# MSSRP-Bluetooth_IF.net
KiCad netlist of a schematic drawn in EAGLE
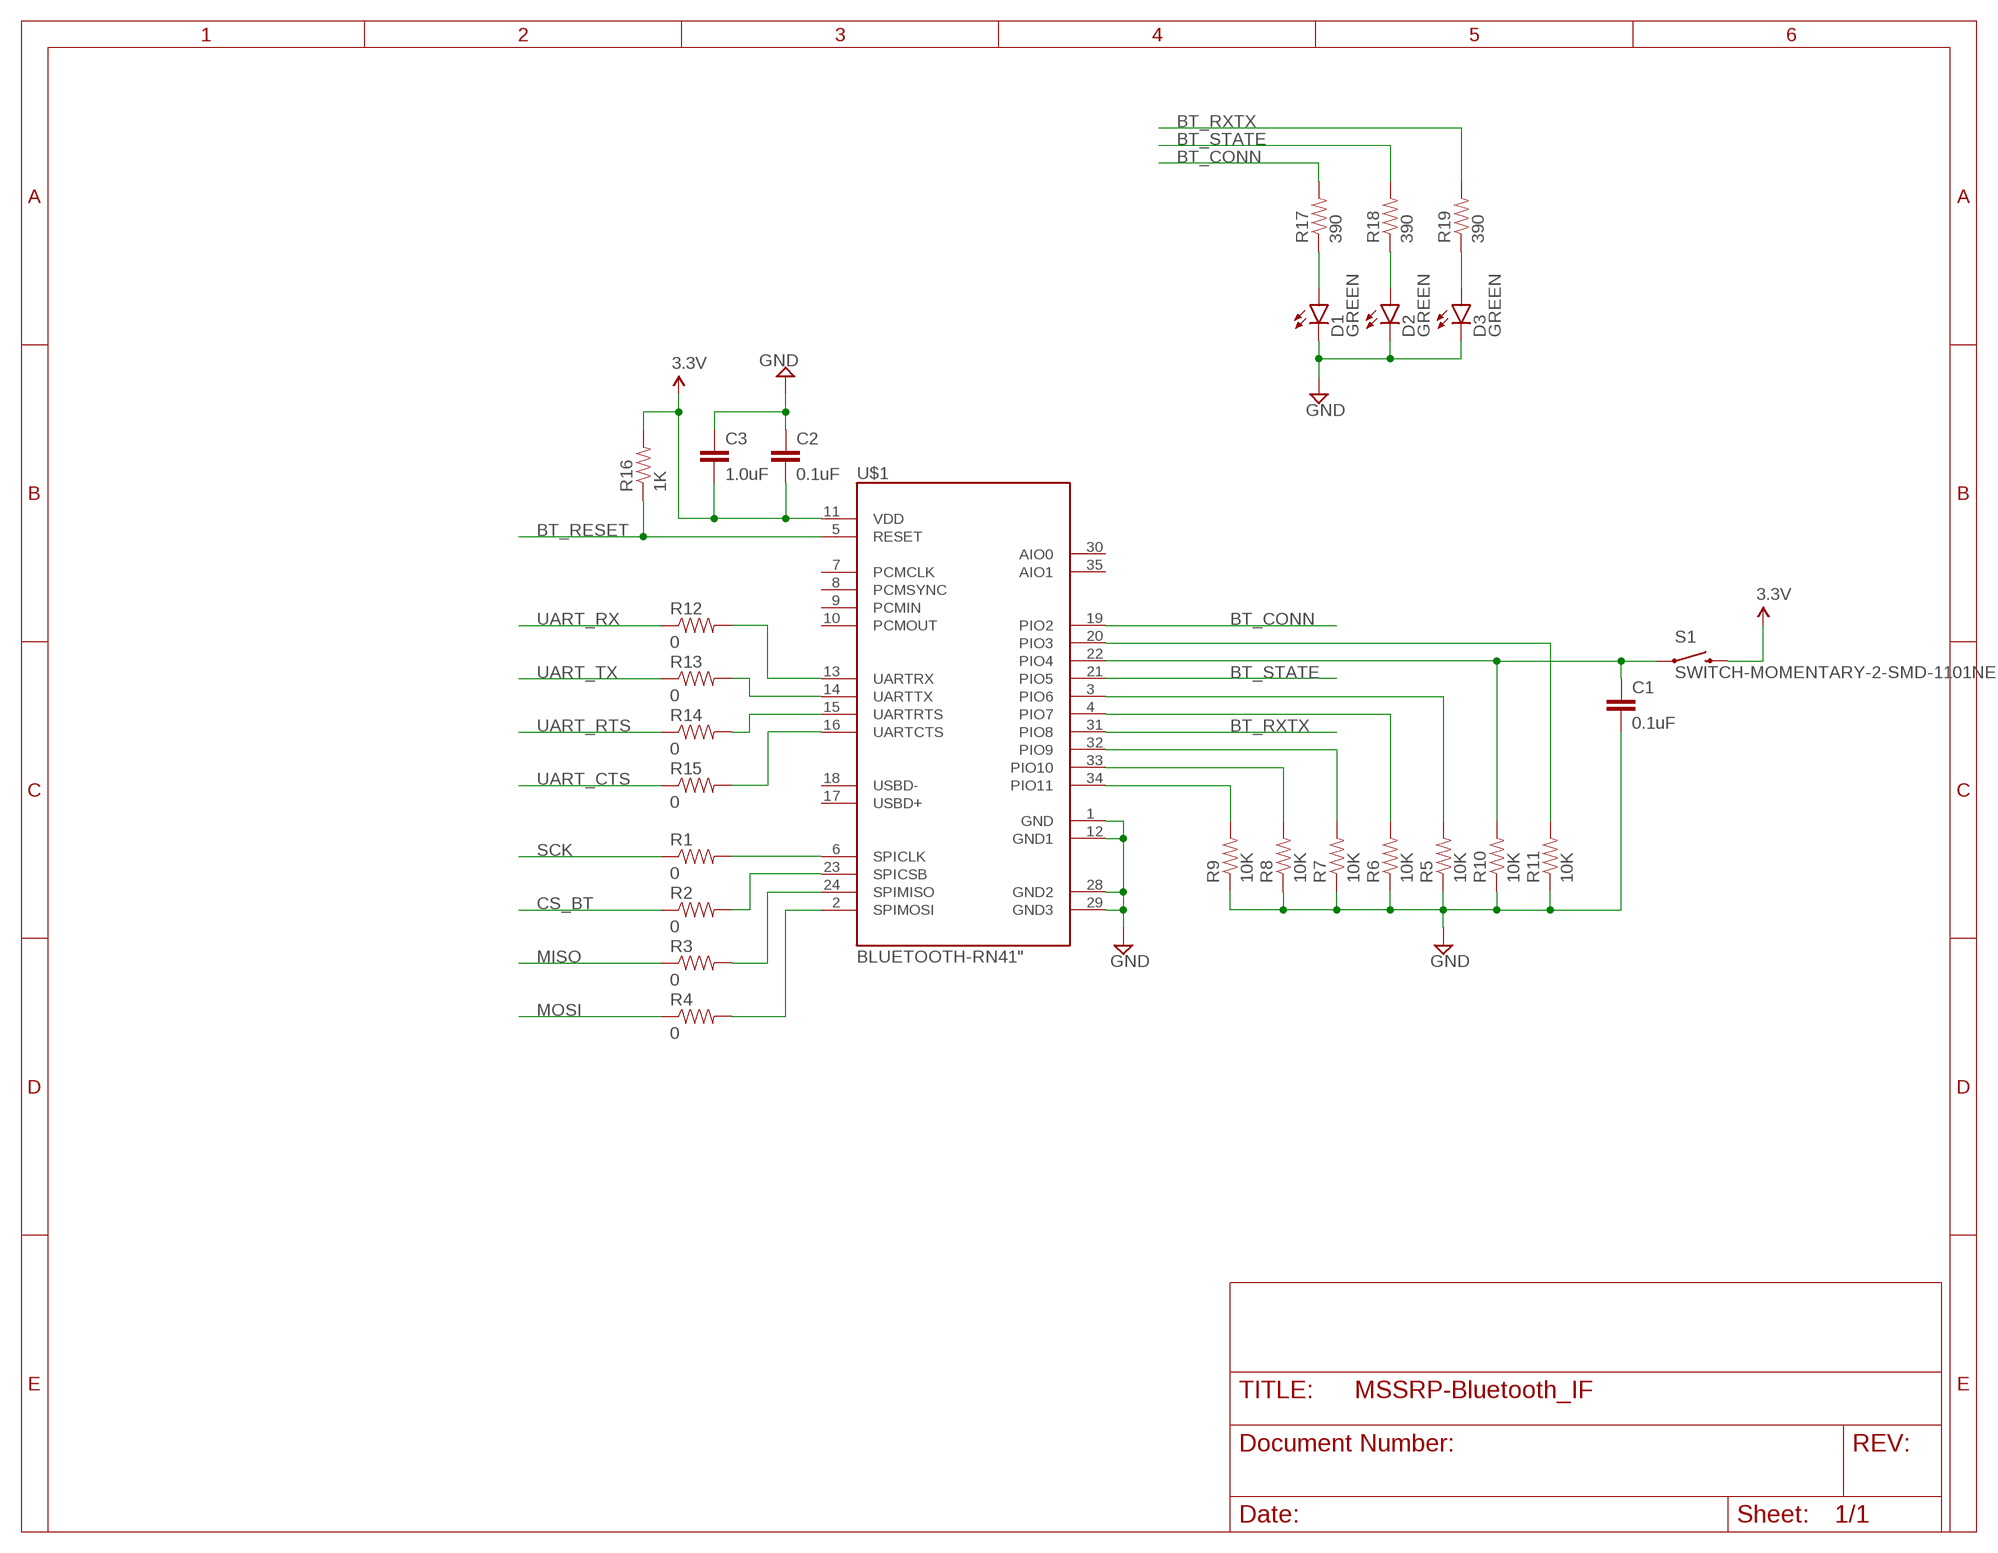
[diagram p0: schematic, sheet 1]

(export (version "E")
  (design (tool "Eeschema 10.0.6"))
  (components
    (comp (ref "C1")
      (value "0.1uF")
      (footprint "eagle-import:0603-CAP")
      (libsource (lib "eagle-import") (part "0.1UF-25V-5%(0603)"))
    )
    (comp (ref "C2")
      (value "0.1uF")
      (footprint "eagle-import:0603-CAP")
      (libsource (lib "eagle-import") (part "0.1UF-25V-5%(0603)"))
    )
    (comp (ref "C3")
      (value "1.0uF")
      (footprint "eagle-import:0603-CAP")
      (libsource (lib "eagle-import") (part "1.0UF-16V-10%(0603)"))
    )
    (comp (ref "D1")
      (value "GREEN")
      (footprint "eagle-import:LED-0603")
      (libsource (lib "eagle-import") (part "LED-GREEN0603"))
    )
    (comp (ref "D2")
      (value "GREEN")
      (footprint "eagle-import:LED-0603")
      (libsource (lib "eagle-import") (part "LED-GREEN0603"))
    )
    (comp (ref "D3")
      (value "GREEN")
      (footprint "eagle-import:LED-0603")
      (libsource (lib "eagle-import") (part "LED-GREEN0603"))
    )
    (comp (ref "R1")
      (value "0")
      (footprint "eagle-import:0603")
      (libsource (lib "eagle-import") (part "0OHM1/10W5%(0603)"))
    )
    (comp (ref "R2")
      (value "0")
      (footprint "eagle-import:0603")
      (libsource (lib "eagle-import") (part "0OHM1/10W5%(0603)"))
    )
    (comp (ref "R3")
      (value "0")
      (footprint "eagle-import:0603")
      (libsource (lib "eagle-import") (part "0OHM1/10W5%(0603)"))
    )
    (comp (ref "R4")
      (value "0")
      (footprint "eagle-import:0603")
      (libsource (lib "eagle-import") (part "0OHM1/10W5%(0603)"))
    )
    (comp (ref "R5")
      (value "10K")
      (footprint "eagle-import:0603-RES")
      (libsource (lib "eagle-import") (part "10KOHM1/10W1%(0603)0603"))
    )
    (comp (ref "R6")
      (value "10K")
      (footprint "eagle-import:0603-RES")
      (libsource (lib "eagle-import") (part "10KOHM1/10W1%(0603)0603"))
    )
    (comp (ref "R7")
      (value "10K")
      (footprint "eagle-import:0603-RES")
      (libsource (lib "eagle-import") (part "10KOHM1/10W1%(0603)0603"))
    )
    (comp (ref "R8")
      (value "10K")
      (footprint "eagle-import:0603-RES")
      (libsource (lib "eagle-import") (part "10KOHM1/10W1%(0603)0603"))
    )
    (comp (ref "R9")
      (value "10K")
      (footprint "eagle-import:0603-RES")
      (libsource (lib "eagle-import") (part "10KOHM1/10W1%(0603)0603"))
    )
    (comp (ref "R10")
      (value "10K")
      (footprint "eagle-import:0603-RES")
      (libsource (lib "eagle-import") (part "10KOHM1/10W1%(0603)0603"))
    )
    (comp (ref "R11")
      (value "10K")
      (footprint "eagle-import:0603-RES")
      (libsource (lib "eagle-import") (part "10KOHM1/10W1%(0603)0603"))
    )
    (comp (ref "R12")
      (value "0")
      (footprint "eagle-import:0603")
      (libsource (lib "eagle-import") (part "0OHM1/10W5%(0603)"))
    )
    (comp (ref "R13")
      (value "0")
      (footprint "eagle-import:0603")
      (libsource (lib "eagle-import") (part "0OHM1/10W5%(0603)"))
    )
    (comp (ref "R14")
      (value "0")
      (footprint "eagle-import:0603")
      (libsource (lib "eagle-import") (part "0OHM1/10W5%(0603)"))
    )
    (comp (ref "R15")
      (value "0")
      (footprint "eagle-import:0603")
      (libsource (lib "eagle-import") (part "0OHM1/10W5%(0603)"))
    )
    (comp (ref "R16")
      (value "1K")
      (footprint "eagle-import:0603-RES")
      (libsource (lib "eagle-import") (part "1KOHM1/10W1%(0603)"))
    )
    (comp (ref "R17")
      (value "390")
      (footprint "eagle-import:0603-RES")
      (libsource (lib "eagle-import") (part "390OHM1/10W1%(0603)"))
    )
    (comp (ref "R18")
      (value "390")
      (footprint "eagle-import:0603-RES")
      (libsource (lib "eagle-import") (part "390OHM1/10W1%(0603)"))
    )
    (comp (ref "R19")
      (value "390")
      (footprint "eagle-import:0603-RES")
      (libsource (lib "eagle-import") (part "390OHM1/10W1%(0603)"))
    )
    (comp (ref "S1")
      (value "SWITCH-MOMENTARY-2-SMD-1101NE")
      (footprint "eagle-import:TACTILE-SWITCH-1101NE")
      (libsource (lib "eagle-import") (part "SWITCH-MOMENTARY-2-SMD-1101NE"))
    )
    (comp (ref "U$1")
      (value "BLUETOOTH-RN41\"")
      (footprint "eagle-import:RN41")
      (libsource (lib "eagle-import") (part "BLUETOOTH-RN41{dblquote}"))
    )
  )
  (nets
    (net (code "1") (name "/BT_CONN") (class "Default")
      (node (ref "R17") (pin "2") (pinfunction "2_2") (pintype "passive"))
      (node (ref "U$1") (pin "19") (pinfunction "PIO2_19") (pintype "bidirectional"))
    )
    (net (code "2") (name "/BT_RESET") (class "Default")
      (node (ref "R16") (pin "1") (pinfunction "1_1") (pintype "passive"))
      (node (ref "U$1") (pin "5") (pinfunction "RESET_5") (pintype "bidirectional"))
    )
    (net (code "3") (name "/BT_RXTX") (class "Default")
      (node (ref "R19") (pin "2") (pinfunction "2_2") (pintype "passive"))
      (node (ref "U$1") (pin "31") (pinfunction "PIO8_31") (pintype "bidirectional"))
    )
    (net (code "4") (name "/BT_STATE") (class "Default")
      (node (ref "R18") (pin "2") (pinfunction "2_2") (pintype "passive"))
      (node (ref "U$1") (pin "21") (pinfunction "PIO5_21") (pintype "bidirectional"))
    )
    (net (code "5") (name "/CS_BT") (class "Default")
      (node (ref "R2") (pin "1") (pinfunction "1_1") (pintype "passive"))
    )
    (net (code "6") (name "/MISO") (class "Default")
      (node (ref "R3") (pin "1") (pinfunction "1_1") (pintype "passive"))
    )
    (net (code "7") (name "/MOSI") (class "Default")
      (node (ref "R4") (pin "1") (pinfunction "1_1") (pintype "passive"))
    )
    (net (code "8") (name "/SCK") (class "Default")
      (node (ref "R1") (pin "1") (pinfunction "1_1") (pintype "passive"))
    )
    (net (code "9") (name "/UART_CTS") (class "Default")
      (node (ref "R15") (pin "1") (pinfunction "1_1") (pintype "passive"))
    )
    (net (code "10") (name "/UART_RTS") (class "Default")
      (node (ref "R14") (pin "1") (pinfunction "1_1") (pintype "passive"))
    )
    (net (code "11") (name "/UART_RX") (class "Default")
      (node (ref "R12") (pin "1") (pinfunction "1_1") (pintype "passive"))
    )
    (net (code "12") (name "/UART_TX") (class "Default")
      (node (ref "R13") (pin "1") (pinfunction "1_1") (pintype "passive"))
    )
    (net (code "13") (name "3.3V") (class "Default")
      (node (ref "C2") (pin "2") (pinfunction "2_2") (pintype "passive"))
      (node (ref "C3") (pin "2") (pinfunction "2_2") (pintype "passive"))
      (node (ref "R16") (pin "2") (pinfunction "2_2") (pintype "passive"))
      (node (ref "S1") (pin "P$2") (pinfunction "2_P$2") (pintype "passive"))
      (node (ref "U$1") (pin "11") (pinfunction "VDD_11") (pintype "bidirectional"))
    )
    (net (code "14") (name "GND") (class "Default")
      (node (ref "C1") (pin "2") (pinfunction "2_2") (pintype "passive"))
      (node (ref "C2") (pin "1") (pinfunction "1_1") (pintype "passive"))
      (node (ref "C3") (pin "1") (pinfunction "1_1") (pintype "passive"))
      (node (ref "D1") (pin "C") (pinfunction "C_C") (pintype "passive"))
      (node (ref "D2") (pin "C") (pinfunction "C_C") (pintype "passive"))
      (node (ref "D3") (pin "C") (pinfunction "C_C") (pintype "passive"))
      (node (ref "R10") (pin "1") (pinfunction "1_1") (pintype "passive"))
      (node (ref "R11") (pin "1") (pinfunction "1_1") (pintype "passive"))
      (node (ref "R5") (pin "1") (pinfunction "1_1") (pintype "passive"))
      (node (ref "R6") (pin "1") (pinfunction "1_1") (pintype "passive"))
      (node (ref "R7") (pin "1") (pinfunction "1_1") (pintype "passive"))
      (node (ref "R8") (pin "1") (pinfunction "1_1") (pintype "passive"))
      (node (ref "R9") (pin "1") (pinfunction "1_1") (pintype "passive"))
      (node (ref "U$1") (pin "1") (pinfunction "GND_1") (pintype "bidirectional"))
      (node (ref "U$1") (pin "12") (pinfunction "GND1_12") (pintype "bidirectional"))
      (node (ref "U$1") (pin "28") (pinfunction "GND2_28") (pintype "bidirectional"))
      (node (ref "U$1") (pin "29") (pinfunction "GND3_29") (pintype "bidirectional"))
    )
    (net (code "15") (name "Net-(D1-PadA)") (class "Default")
      (node (ref "D1") (pin "A") (pinfunction "A_A") (pintype "passive"))
      (node (ref "R17") (pin "1") (pinfunction "1_1") (pintype "passive"))
    )
    (net (code "16") (name "Net-(D2-PadA)") (class "Default")
      (node (ref "D2") (pin "A") (pinfunction "A_A") (pintype "passive"))
      (node (ref "R18") (pin "1") (pinfunction "1_1") (pintype "passive"))
    )
    (net (code "17") (name "Net-(D3-PadA)") (class "Default")
      (node (ref "D3") (pin "A") (pinfunction "A_A") (pintype "passive"))
      (node (ref "R19") (pin "1") (pinfunction "1_1") (pintype "passive"))
    )
    (net (code "18") (name "Net-(S1-1)") (class "Default")
      (node (ref "C1") (pin "1") (pinfunction "1_1") (pintype "passive"))
      (node (ref "R10") (pin "2") (pinfunction "2_2") (pintype "passive"))
      (node (ref "S1") (pin "P$1") (pinfunction "1_P$1") (pintype "passive"))
      (node (ref "U$1") (pin "22") (pinfunction "PIO4_22") (pintype "bidirectional"))
    )
    (net (code "19") (name "Net-(U$1-PIO3)") (class "Default")
      (node (ref "R11") (pin "2") (pinfunction "2_2") (pintype "passive"))
      (node (ref "U$1") (pin "20") (pinfunction "PIO3_20") (pintype "bidirectional"))
    )
    (net (code "20") (name "Net-(U$1-PIO6)") (class "Default")
      (node (ref "R5") (pin "2") (pinfunction "2_2") (pintype "passive"))
      (node (ref "U$1") (pin "3") (pinfunction "PIO6_3") (pintype "bidirectional"))
    )
    (net (code "21") (name "Net-(U$1-PIO7)") (class "Default")
      (node (ref "R6") (pin "2") (pinfunction "2_2") (pintype "passive"))
      (node (ref "U$1") (pin "4") (pinfunction "PIO7_4") (pintype "bidirectional"))
    )
    (net (code "22") (name "Net-(U$1-PIO9)") (class "Default")
      (node (ref "R7") (pin "2") (pinfunction "2_2") (pintype "passive"))
      (node (ref "U$1") (pin "32") (pinfunction "PIO9_32") (pintype "bidirectional"))
    )
    (net (code "23") (name "Net-(U$1-PIO10)") (class "Default")
      (node (ref "R8") (pin "2") (pinfunction "2_2") (pintype "passive"))
      (node (ref "U$1") (pin "33") (pinfunction "PIO10_33") (pintype "bidirectional"))
    )
    (net (code "24") (name "Net-(U$1-PIO11)") (class "Default")
      (node (ref "R9") (pin "2") (pinfunction "2_2") (pintype "passive"))
      (node (ref "U$1") (pin "34") (pinfunction "PIO11_34") (pintype "bidirectional"))
    )
    (net (code "25") (name "Net-(U$1-SPICLK)") (class "Default")
      (node (ref "R1") (pin "2") (pinfunction "2_2") (pintype "passive"))
      (node (ref "U$1") (pin "6") (pinfunction "SPICLK_6") (pintype "bidirectional"))
    )
    (net (code "26") (name "Net-(U$1-SPICSB)") (class "Default")
      (node (ref "R2") (pin "2") (pinfunction "2_2") (pintype "passive"))
      (node (ref "U$1") (pin "23") (pinfunction "SPICSB_23") (pintype "bidirectional"))
    )
    (net (code "27") (name "Net-(U$1-SPIMISO)") (class "Default")
      (node (ref "R3") (pin "2") (pinfunction "2_2") (pintype "passive"))
      (node (ref "U$1") (pin "24") (pinfunction "SPIMISO_24") (pintype "bidirectional"))
    )
    (net (code "28") (name "Net-(U$1-SPIMOSI)") (class "Default")
      (node (ref "R4") (pin "2") (pinfunction "2_2") (pintype "passive"))
      (node (ref "U$1") (pin "2") (pinfunction "SPIMOSI_2") (pintype "bidirectional"))
    )
    (net (code "29") (name "Net-(U$1-UARTCTS)") (class "Default")
      (node (ref "R15") (pin "2") (pinfunction "2_2") (pintype "passive"))
      (node (ref "U$1") (pin "16") (pinfunction "UARTCTS_16") (pintype "bidirectional"))
    )
    (net (code "30") (name "Net-(U$1-UARTRTS)") (class "Default")
      (node (ref "R14") (pin "2") (pinfunction "2_2") (pintype "passive"))
      (node (ref "U$1") (pin "15") (pinfunction "UARTRTS_15") (pintype "bidirectional"))
    )
    (net (code "31") (name "Net-(U$1-UARTRX)") (class "Default")
      (node (ref "R12") (pin "2") (pinfunction "2_2") (pintype "passive"))
      (node (ref "U$1") (pin "13") (pinfunction "UARTRX_13") (pintype "bidirectional"))
    )
    (net (code "32") (name "Net-(U$1-UARTTX)") (class "Default")
      (node (ref "R13") (pin "2") (pinfunction "2_2") (pintype "passive"))
      (node (ref "U$1") (pin "14") (pinfunction "UARTTX_14") (pintype "bidirectional"))
    )
    (net (code "33") (name "unconnected-(U$1-AIO0-Pad30)") (class "Default")
      (node (ref "U$1") (pin "30") (pinfunction "AIO0_30") (pintype "bidirectional"))
    )
    (net (code "34") (name "unconnected-(U$1-AIO1-Pad35)") (class "Default")
      (node (ref "U$1") (pin "35") (pinfunction "AIO1_35") (pintype "bidirectional"))
    )
    (net (code "35") (name "unconnected-(U$1-PCMCLK-Pad7)") (class "Default")
      (node (ref "U$1") (pin "7") (pinfunction "PCMCLK_7") (pintype "bidirectional"))
    )
    (net (code "36") (name "unconnected-(U$1-PCMIN-Pad9)") (class "Default")
      (node (ref "U$1") (pin "9") (pinfunction "PCMIN_9") (pintype "bidirectional"))
    )
    (net (code "37") (name "unconnected-(U$1-PCMOUT-Pad10)") (class "Default")
      (node (ref "U$1") (pin "10") (pinfunction "PCMOUT_10") (pintype "bidirectional"))
    )
    (net (code "38") (name "unconnected-(U$1-PCMSYNC-Pad8)") (class "Default")
      (node (ref "U$1") (pin "8") (pinfunction "PCMSYNC_8") (pintype "bidirectional"))
    )
    (net (code "39") (name "unconnected-(U$1-USBD+-Pad17)") (class "Default")
      (node (ref "U$1") (pin "17") (pinfunction "USBD+_17") (pintype "bidirectional"))
    )
    (net (code "40") (name "unconnected-(U$1-USBD--Pad18)") (class "Default")
      (node (ref "U$1") (pin "18") (pinfunction "USBD-_18") (pintype "bidirectional"))
    )
  )
)
